# Protopanda_EasyEda_project.net
KiCad netlist of a schematic drawn in EasyEDA
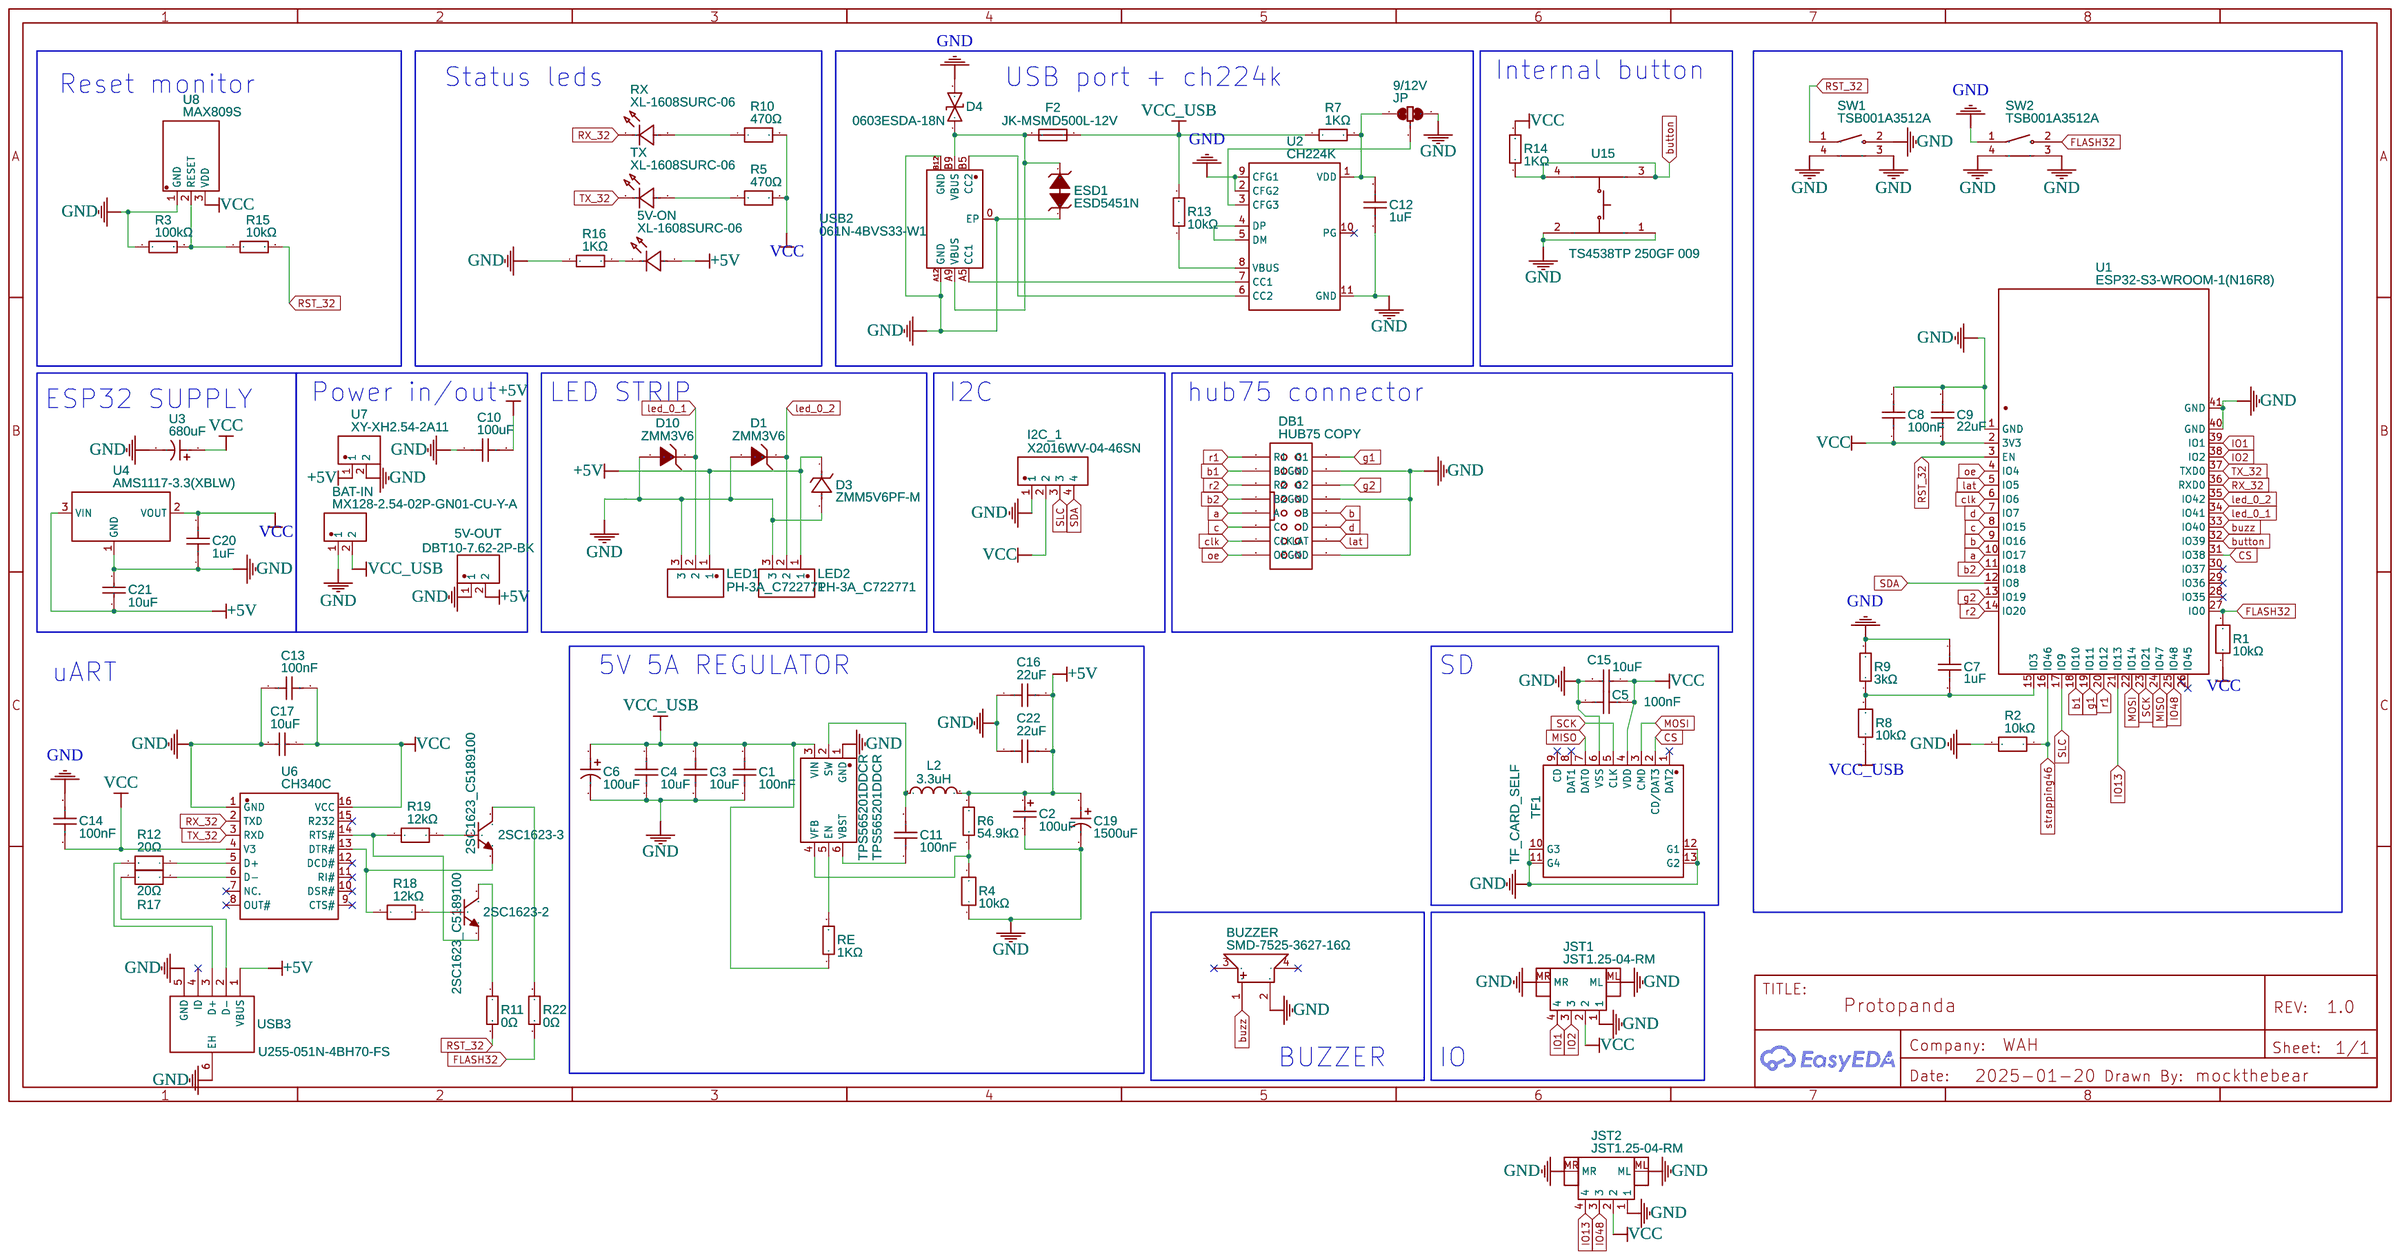
[diagram p0: schematic sheet]

(export (version "E")
  (design (tool "Eeschema 10.0.6"))
  (components
    (comp (ref "2SC1623-2")
      (value "2SC1623_C5189100")
      (fields (field (name "Manufacturer Part") "2SC1623") (field (name "Manufacturer") "HXY MOSFET(华轩阳电子)"))
      (libsource (lib "") (part "2SC1623_C5189100"))
    )
    (comp (ref "2SC1623-3")
      (value "2SC1623_C5189100")
      (fields (field (name "Manufacturer Part") "2SC1623") (field (name "Manufacturer") "HXY MOSFET(华轩阳电子)"))
      (libsource (lib "") (part "2SC1623_C5189100"))
    )
    (comp (ref "5V-ON")
      (value "XL-1608SURC-06")
      (fields (field (name "Manufacturer") "XINGLIGHT(成兴光)"))
      (libsource (lib "") (part "XL-1608SURC-06_2"))
    )
    (comp (ref "5V-OUT")
      (value "DBT10-7.62-2P-BK")
      (fields
        (field (name "Manufacturer Part") "DBT10-7.62-2P-BK-P")
        (field (name "Manufacturer") "DORABO(地博电气)")
      )
      (libsource (lib "") (part "DBT10-7.62-2P-BK"))
    )
    (comp (ref "9/12V") (value "JP") (libsource (lib "") (part "JUMPER-PAD-3-NOFULL_BOX_SILK")))
    (comp (ref "BAT-IN")
      (value "MX128-2.54-02P-GN01-CU-Y-A")
      (fields
        (field (name "Manufacturer Part") "MX128-2.54-02P-GN01-Cu-Y-A")
        (field (name "Manufacturer") "MAX(迈旭)")
      )
      (libsource (lib "") (part "MX128-2.54-02P-GN01-CU-Y-A"))
    )
    (comp (ref "BUZZER")
      (value "SMD-7525-3627-16Ω")
      (fields (field (name "Manufacturer") "S&S(海旭)"))
      (libsource (lib "") (part "SMD-7525-3627-16Ω"))
    )
    (comp (ref "C1")
      (value "100nF")
      (fields
        (field (name "Manufacturer Part") "CC0603KRX7R6BB104")
        (field (name "Manufacturer") "YAGEO(国巨)")
      )
      (libsource (lib "") (part "CC0603KRX7R6BB104_1"))
    )
    (comp (ref "C2")
      (value "100uF")
      (fields
        (field (name "Manufacturer Part") "T490A107M006ATE800")
        (field (name "Manufacturer") "KEMET(基美)")
      )
      (libsource (lib "") (part "T490A107M006ATE800"))
    )
    (comp (ref "C3")
      (value "10uF")
      (fields (field (name "Manufacturer Part") "CC0603CRNPO9BN5R1") (field (name "Manufacturer") "YAGEO"))
      (libsource (lib "") (part "CC0603CRNPO9BN5R1"))
    )
    (comp (ref "C4")
      (value "10uF")
      (fields (field (name "Manufacturer Part") "CC0603CRNPO9BN5R1") (field (name "Manufacturer") "YAGEO"))
      (libsource (lib "") (part "CC0603CRNPO9BN5R1"))
    )
    (comp (ref "C5")
      (value "100nF")
      (fields
        (field (name "Manufacturer Part") "CC0603KRX7R6BB104")
        (field (name "Manufacturer") "YAGEO(国巨)")
      )
      (libsource (lib "") (part "CC0603KRX7R6BB104"))
    )
    (comp (ref "C6")
      (value "100uF")
      (fields
        (field (name "Manufacturer Part") "RVT100UF25V67RV0011")
        (field (name "Manufacturer") "KNSCHA(科尼盛)")
      )
      (libsource (lib "") (part "RVT100UF25V67RV0011"))
    )
    (comp (ref "C7")
      (value "1uF")
      (fields
        (field (name "Manufacturer Part") "CS1608X7R105K250NRB")
        (field (name "Manufacturer") "Samwha Capacitor")
      )
      (libsource (lib "") (part "CS1608X7R105K250NRB"))
    )
    (comp (ref "C8")
      (value "100nF")
      (fields
        (field (name "Manufacturer Part") "CC0603KRX7R6BB104")
        (field (name "Manufacturer") "YAGEO(国巨)")
      )
      (libsource (lib "") (part "CC0603KRX7R6BB104_1"))
    )
    (comp (ref "C9")
      (value "22uF")
      (fields
        (field (name "Manufacturer Part") "GRM188R61A226ME15D")
        (field (name "Manufacturer") "muRata(村田)")
      )
      (libsource (lib "") (part "GRM188R61A226ME15D"))
    )
    (comp (ref "C10")
      (value "100uF")
      (fields
        (field (name "Manufacturer Part") "TCC1206X5R107M6R3HT")
        (field (name "Manufacturer") "CCTC(三环)")
      )
      (libsource (lib "") (part "TCC1206X5R107M6R3HT"))
    )
    (comp (ref "C11")
      (value "100nF")
      (fields
        (field (name "Manufacturer Part") "CC0603KRX7R6BB104")
        (field (name "Manufacturer") "YAGEO(国巨)")
      )
      (libsource (lib "") (part "CC0603KRX7R6BB104_1"))
    )
    (comp (ref "C12")
      (value "1uF")
      (fields (field (name "Manufacturer Part") "CC0603CRNPO9BN5R1") (field (name "Manufacturer") "YAGEO"))
      (libsource (lib "") (part "CC0603CRNPO9BN5R1"))
    )
    (comp (ref "C13")
      (value "100nF")
      (fields
        (field (name "Manufacturer Part") "CC0603KRX7R6BB104")
        (field (name "Manufacturer") "YAGEO(国巨)")
      )
      (libsource (lib "") (part "CC0603KRX7R6BB104"))
    )
    (comp (ref "C14")
      (value "100nF")
      (fields
        (field (name "Manufacturer Part") "CC0603KRX7R6BB104")
        (field (name "Manufacturer") "YAGEO(国巨)")
      )
      (libsource (lib "") (part "CC0603KRX7R6BB104_1"))
    )
    (comp (ref "C15")
      (value "10uF")
      (fields (field (name "Manufacturer Part") "CC0603MRX5R6BB106") (field (name "Manufacturer") "YAGEO"))
      (libsource (lib "") (part "CC0603MRX5R6BB106"))
    )
    (comp (ref "C16") (value "22uF") (libsource (lib "") (part "C_0805_US")))
    (comp (ref "C17")
      (value "10uF")
      (fields (field (name "Manufacturer Part") "CC0603KRX5R5BB106") (field (name "Manufacturer") "YAGEO"))
      (libsource (lib "") (part "CC0603KRX5R5BB106"))
    )
    (comp (ref "C19")
      (value "1500uF")
      (fields (field (name "Manufacturer Part") "189RV0022") (field (name "Manufacturer") "KNSCHA(科尼盛)"))
      (libsource (lib "") (part "189RV0022"))
    )
    (comp (ref "C20")
      (value "1uF")
      (fields
        (field (name "Manufacturer Part") "CS1608X7R105K250NRB")
        (field (name "Manufacturer") "Samwha Capacitor")
      )
      (libsource (lib "") (part "CS1608X7R105K250NRB_1"))
    )
    (comp (ref "C21")
      (value "10uF")
      (fields (field (name "Manufacturer Part") "CC0603MRX5R6BB106") (field (name "Manufacturer") "YAGEO"))
      (libsource (lib "") (part "CC0603MRX5R6BB106_1"))
    )
    (comp (ref "C22") (value "22uF") (libsource (lib "") (part "C_0805_US")))
    (comp (ref "D1")
      (value "ZMM3V6")
      (fields (field (name "Manufacturer Part") "ZMM3V6-M") (field (name "Manufacturer") "ST(先科)"))
      (libsource (lib "") (part "ZMM3V6"))
    )
    (comp (ref "D3")
      (value "ZMM5V6PF-M")
      (fields (field (name "Manufacturer") "ST(先科)"))
      (libsource (lib "") (part "ZMM5V6PF-M"))
    )
    (comp (ref "D4")
      (value "0603ESDA-18N")
      (fields (field (name "Manufacturer") "BORN(伯恩半导体)"))
      (libsource (lib "") (part "0603ESDA-18N"))
    )
    (comp (ref "D10")
      (value "ZMM3V6")
      (fields (field (name "Manufacturer Part") "ZMM3V6-M") (field (name "Manufacturer") "ST(先科)"))
      (libsource (lib "") (part "ZMM3V6"))
    )
    (comp (ref "DB1") (value "HUB75 COPY") (libsource (lib "") (part "HUB75 COPY")))
    (comp (ref "ESD1")
      (value "ESD5451N")
      (fields (field (name "Manufacturer") "UMW(广东友台半导体)"))
      (libsource (lib "") (part "ESD5451N"))
    )
    (comp (ref "F2")
      (value "JK-MSMD500L-12V")
      (fields (field (name "Manufacturer") "JK(金科)"))
      (libsource (lib "") (part "JK-MSMD500L-12V"))
    )
    (comp (ref "I2C_1")
      (value "X2016WV-04-46SN")
      (fields (field (name "Manufacturer") "XKB Connectivity(中国星坤)"))
      (libsource (lib "") (part "X2016WV-04-46SN"))
    )
    (comp (ref "JST1") (value "JST1.25-04-RM") (libsource (lib "") (part "JST1.25-04-RM")))
    (comp (ref "JST2") (value "JST1.25-04-RM") (libsource (lib "") (part "JST1.25-04-RM")))
    (comp (ref "L2")
      (value "3.3uH")
      (fields
        (field (name "Manufacturer Part") "PSPMAA1040H-3R3M-ANP")
        (field (name "Manufacturer") "PROD(谱罗德)")
      )
      (libsource (lib "") (part "PSPMAA1040H-3R3M-ANP"))
    )
    (comp (ref "LED1")
      (value "PH-3A_C722771")
      (fields (field (name "Manufacturer Part") "PH-3A") (field (name "Manufacturer") "CAX(创都)"))
      (libsource (lib "") (part "PH-3A_C722771"))
    )
    (comp (ref "LED2")
      (value "PH-3A_C722771")
      (fields (field (name "Manufacturer Part") "PH-3A") (field (name "Manufacturer") "CAX(创都)"))
      (libsource (lib "") (part "PH-3A_C722771"))
    )
    (comp (ref "R1")
      (value "10kΩ")
      (fields (field (name "Manufacturer Part") "FRC0603F4992TS") (field (name "Manufacturer") "FOJAN(富捷)"))
      (libsource (lib "") (part "FRC0603F4992TS"))
    )
    (comp (ref "R2")
      (value "10kΩ")
      (fields (field (name "Manufacturer Part") "FRC0603F4992TS") (field (name "Manufacturer") "FOJAN(富捷)"))
      (libsource (lib "") (part "FRC0603F4992TS_1"))
    )
    (comp (ref "R3")
      (value "100kΩ")
      (fields
        (field (name "Manufacturer Part") "CL0603JN100KP")
        (field (name "Manufacturer") "ResistorToday")
      )
      (libsource (lib "") (part "PTFR0603B10K0P9_1"))
    )
    (comp (ref "R4")
      (value "10kΩ")
      (fields (field (name "Manufacturer Part") "FRC0603F4992TS") (field (name "Manufacturer") "FOJAN(富捷)"))
      (libsource (lib "") (part "FRC0603F4992TS"))
    )
    (comp (ref "R5")
      (value "470Ω")
      (fields (field (name "Manufacturer Part") "CL0603JN470RP") (field (name "Manufacturer") "昶龙科技"))
      (libsource (lib "") (part "CL0603JN470RP"))
    )
    (comp (ref "R6")
      (value "54.9kΩ")
      (fields
        (field (name "Manufacturer Part") "RCT03365KFLF")
        (field (name "Manufacturer") "Hong Kong Resistors")
      )
      (libsource (lib "") (part "RCT03365KFLF"))
    )
    (comp (ref "R7")
      (value "1KΩ")
      (fields (field (name "Manufacturer Part") "HRC0603J102 ENTN") (field (name "Manufacturer") "HWA CHN"))
      (libsource (lib "") (part "CR0603FA56R0G"))
    )
    (comp (ref "R8")
      (value "10kΩ")
      (fields (field (name "Manufacturer Part") "FRC0603F4992TS") (field (name "Manufacturer") "FOJAN(富捷)"))
      (libsource (lib "") (part "FRC0603F4992TS"))
    )
    (comp (ref "R9")
      (value "3kΩ")
      (fields (field (name "Manufacturer Part") "RTT03302JTP") (field (name "Manufacturer") "RALEC(旺诠)"))
      (libsource (lib "") (part "RTT03302JTP"))
    )
    (comp (ref "R10")
      (value "470Ω")
      (fields (field (name "Manufacturer Part") "CL0603JN470RP") (field (name "Manufacturer") "昶龙科技"))
      (libsource (lib "") (part "CL0603JN470RP"))
    )
    (comp (ref "R11")
      (value "0Ω")
      (fields
        (field (name "Manufacturer Part") "AECR0603F100RK9")
        (field (name "Manufacturer") "ResistorToday")
      )
      (libsource (lib "") (part "AECR0603F100RK9"))
    )
    (comp (ref "R12")
      (value "20Ω")
      (fields (field (name "Manufacturer Part") "SCR0603F20R") (field (name "Manufacturer") "VO(翔胜)"))
      (libsource (lib "") (part "SCR0603F20R_1"))
    )
    (comp (ref "R13")
      (value "10kΩ")
      (fields
        (field (name "Manufacturer Part") "PTFR0603B10K0P9")
        (field (name "Manufacturer") "ResistorToday")
      )
      (libsource (lib "") (part "PTFR0603B10K0P9"))
    )
    (comp (ref "R14")
      (value "1KΩ")
      (fields (field (name "Manufacturer Part") "HRC0603J102 ENTN") (field (name "Manufacturer") "HWA CHN"))
      (libsource (lib "") (part "CR0603FA56R0G_1"))
    )
    (comp (ref "R15")
      (value "10kΩ")
      (fields
        (field (name "Manufacturer Part") "PTFR0603B10K0P9")
        (field (name "Manufacturer") "ResistorToday")
      )
      (libsource (lib "") (part "PTFR0603B10K0P9_1"))
    )
    (comp (ref "R16")
      (value "1KΩ")
      (fields (field (name "Manufacturer Part") "HRC0603J102 ENTN") (field (name "Manufacturer") "HWA CHN"))
      (libsource (lib "") (part "CR0603FA56R0G"))
    )
    (comp (ref "R17")
      (value "20Ω")
      (fields (field (name "Manufacturer Part") "SCR0603F20R") (field (name "Manufacturer") "VO(翔胜)"))
      (libsource (lib "") (part "SCR0603F20R"))
    )
    (comp (ref "R18")
      (value "12kΩ")
      (fields (field (name "Manufacturer Part") "FRC0603J123 TS") (field (name "Manufacturer") "FOJAN(富捷)"))
      (libsource (lib "") (part "FRC0603J123 TS"))
    )
    (comp (ref "R19")
      (value "12kΩ")
      (fields (field (name "Manufacturer Part") "FRC0603J123 TS") (field (name "Manufacturer") "FOJAN(富捷)"))
      (libsource (lib "") (part "FRC0603J123 TS"))
    )
    (comp (ref "R22")
      (value "0Ω")
      (fields
        (field (name "Manufacturer Part") "AECR0603F100RK9")
        (field (name "Manufacturer") "ResistorToday")
      )
      (libsource (lib "") (part "AECR0603F100RK9_1"))
    )
    (comp (ref "RE")
      (value "1KΩ")
      (fields (field (name "Manufacturer Part") "HRC0603J102 ENTN") (field (name "Manufacturer") "HWA CHN"))
      (libsource (lib "") (part "CR0603FA56R0G_2"))
    )
    (comp (ref "RX")
      (value "XL-1608SURC-06")
      (fields (field (name "Manufacturer") "XINGLIGHT(成兴光)"))
      (libsource (lib "") (part "XL-1608SURC-06_1"))
    )
    (comp (ref "SW1")
      (value "TSB001A3512A")
      (fields (field (name "Manufacturer") "BZCN(博众电气)"))
      (libsource (lib "") (part "TSB001A3512A"))
    )
    (comp (ref "SW2")
      (value "TSB001A3512A")
      (fields (field (name "Manufacturer") "BZCN(博众电气)"))
      (libsource (lib "") (part "TSB001A3512A"))
    )
    (comp (ref "TF1") (value "TF_CARD_SELF") (libsource (lib "") (part "TF_CARD_SELF")))
    (comp (ref "TPS565201DDCR")
      (value "TPS565201DDCR")
      (fields (field (name "Manufacturer") "TI(德州仪器)"))
      (libsource (lib "") (part "TPS565201DDCR"))
    )
    (comp (ref "TX")
      (value "XL-1608SURC-06")
      (fields (field (name "Manufacturer") "XINGLIGHT(成兴光)"))
      (libsource (lib "") (part "XL-1608SURC-06"))
    )
    (comp (ref "U1")
      (value "ESP32-S3-WROOM-1(N16R8)")
      (fields
        (field (name "Manufacturer Part") "ESP32-S3-WROOM-1-N16R8")
        (field (name "Manufacturer") "ESPRESSIF(乐鑫)")
      )
      (libsource (lib "") (part "ESP32-S3-WROOM-1(N16R8)"))
    )
    (comp (ref "U2")
      (value "CH224K")
      (fields (field (name "Manufacturer") "WCH(南京沁恒)"))
      (libsource (lib "") (part "CH224K"))
    )
    (comp (ref "U3")
      (value "680uF")
      (fields (field (name "Manufacturer Part") "189RV0015") (field (name "Manufacturer") "KNSCHA(科尼盛)"))
      (libsource (lib "") (part "189RV0015"))
    )
    (comp (ref "U4")
      (value "AMS1117-3.3(XBLW)")
      (fields (field (name "Manufacturer") "XBLW(芯伯乐)"))
      (libsource (lib "") (part "AMS1117-3.3(XBLW)"))
    )
    (comp (ref "U6")
      (value "CH340C")
      (fields (field (name "Manufacturer") "WCH(南京沁恒)"))
      (libsource (lib "") (part "CH340C"))
    )
    (comp (ref "U7")
      (value "XY-XH2.54-2A11")
      (fields (field (name "Manufacturer") "XYECONN(辛译)"))
      (libsource (lib "") (part "XY-XH2.54-2A11"))
    )
    (comp (ref "U8")
      (value "MAX809S")
      (fields (field (name "Manufacturer") "UMW(广东友台半导体)"))
      (libsource (lib "") (part "MAX809S"))
    )
    (comp (ref "U15")
      (value "TS4538TP 250GF 009")
      (fields
        (field (name "Manufacturer Part") "TS4538TP 250gf 009")
        (field (name "Manufacturer") "SHOU HAN(首韩)")
      )
      (libsource (lib "") (part "TS4538TP 250GF 009"))
    )
    (comp (ref "USB2")
      (value "061N-4BVS33-W1")
      (fields (field (name "Manufacturer") "HanElectricity(瀚源)"))
      (libsource (lib "") (part "061N-4BVS33-W1"))
    )
    (comp (ref "USB3")
      (value "U255-051N-4BH70-FS")
      (fields (field (name "Manufacturer") "XKB Connection(中国星坤)"))
      (libsource (lib "") (part "U255-051N-4BH70-FS"))
    )
  )
  (nets
    (net (code "1") (name "+5V") (class "Default")
      (node (ref "5V-ON") (pin "2") (pinfunction "A_2") (pintype "unspecified"))
      (node (ref "5V-OUT") (pin "2") (pinfunction "2_2") (pintype "unspecified"))
      (node (ref "C10") (pin "2") (pinfunction "2_2") (pintype "unspecified"))
      (node (ref "C16") (pin "2") (pinfunction "2_2") (pintype "unspecified"))
      (node (ref "C19") (pin "1") (pinfunction "1_1") (pintype "input"))
      (node (ref "C2") (pin "1") (pinfunction "1_1") (pintype "input"))
      (node (ref "C21") (pin "2") (pinfunction "2_2") (pintype "input"))
      (node (ref "C22") (pin "2") (pinfunction "2_2") (pintype "unspecified"))
      (node (ref "D3") (pin "1") (pinfunction "C_1") (pintype "unspecified"))
      (node (ref "L2") (pin "2") (pinfunction "2_2") (pintype "unspecified"))
      (node (ref "LED1") (pin "1") (pinfunction "1_1") (pintype "unspecified"))
      (node (ref "LED2") (pin "1") (pinfunction "1_1") (pintype "unspecified"))
      (node (ref "R6") (pin "2") (pinfunction "2_2") (pintype "unspecified"))
      (node (ref "U4") (pin "3") (pinfunction "VIN_3") (pintype "unspecified"))
      (node (ref "U7") (pin "1") (pinfunction "1_1") (pintype "unspecified"))
      (node (ref "USB3") (pin "1") (pinfunction "VBUS_1") (pintype "unspecified"))
    )
    (net (code "2") (name "CS") (class "Default")
      (node (ref "TF1") (pin "2") (pinfunction "CD/DAT3_2") (pintype "unspecified"))
      (node (ref "U1") (pin "31") (pinfunction "IO38_31") (pintype "unspecified"))
    )
    (net (code "3") (name "FLASH32") (class "Default")
      (node (ref "R1") (pin "2") (pinfunction "2_2") (pintype "unspecified"))
      (node (ref "R22") (pin "1") (pinfunction "1_1") (pintype "unspecified"))
      (node (ref "SW2") (pin "2") (pinfunction "2_2") (pintype "unspecified"))
      (node (ref "U1") (pin "27") (pinfunction "IO0_27") (pintype "unspecified"))
    )
    (net (code "4") (name "GND") (class "Default")
      (node (ref "5V-OUT") (pin "1") (pinfunction "1_1") (pintype "unspecified"))
      (node (ref "9/12V") (pin "3") (pinfunction "3_3") (pintype "unspecified"))
      (node (ref "BAT-IN") (pin "1") (pinfunction "1_1") (pintype "unspecified"))
      (node (ref "BUZZER") (pin "2") (pinfunction "2_2") (pintype "unspecified"))
      (node (ref "C1") (pin "1") (pinfunction "1_1") (pintype "unspecified"))
      (node (ref "C10") (pin "1") (pinfunction "1_1") (pintype "unspecified"))
      (node (ref "C12") (pin "2") (pinfunction "2_2") (pintype "unspecified"))
      (node (ref "C13") (pin "1") (pinfunction "1_1") (pintype "unspecified"))
      (node (ref "C14") (pin "2") (pinfunction "2_2") (pintype "unspecified"))
      (node (ref "C15") (pin "2") (pinfunction "2_2") (pintype "input"))
      (node (ref "C16") (pin "1") (pinfunction "1_1") (pintype "unspecified"))
      (node (ref "C17") (pin "2") (pinfunction "2_2") (pintype "input"))
      (node (ref "C19") (pin "2") (pinfunction "2_2") (pintype "input"))
      (node (ref "C2") (pin "2") (pinfunction "2_2") (pintype "input"))
      (node (ref "C20") (pin "1") (pinfunction "1_1") (pintype "unspecified"))
      (node (ref "C21") (pin "1") (pinfunction "1_1") (pintype "input"))
      (node (ref "C22") (pin "1") (pinfunction "1_1") (pintype "unspecified"))
      (node (ref "C3") (pin "2") (pinfunction "2_2") (pintype "unspecified"))
      (node (ref "C4") (pin "2") (pinfunction "2_2") (pintype "unspecified"))
      (node (ref "C5") (pin "1") (pinfunction "1_1") (pintype "unspecified"))
      (node (ref "C6") (pin "2") (pinfunction "2_2") (pintype "input"))
      (node (ref "C7") (pin "1") (pinfunction "1_1") (pintype "unspecified"))
      (node (ref "C8") (pin "2") (pinfunction "2_2") (pintype "unspecified"))
      (node (ref "C9") (pin "1") (pinfunction "1_1") (pintype "unspecified"))
      (node (ref "D1") (pin "2") (pinfunction "A_2") (pintype "unspecified"))
      (node (ref "D10") (pin "2") (pinfunction "A_2") (pintype "unspecified"))
      (node (ref "D3") (pin "2") (pinfunction "A_2") (pintype "unspecified"))
      (node (ref "D4") (pin "2") (pinfunction "2_2") (pintype "unspecified"))
      (node (ref "DB1") (pin "13") (pinfunction "GND_13") (pintype "unspecified"))
      (node (ref "DB1") (pin "15") (pinfunction "GND_15") (pintype "unspecified"))
      (node (ref "DB1") (pin "9") (pinfunction "GND_9") (pintype "unspecified"))
      (node (ref "ESD1") (pin "1") (pinfunction "1_1") (pintype "unspecified"))
      (node (ref "I2C_1") (pin "1") (pinfunction "1_1") (pintype "unspecified"))
      (node (ref "JST1") (pin "1") (pinfunction "1_1") (pintype "unspecified"))
      (node (ref "JST1") (pin "ML") (pinfunction "ML_ML") (pintype "unspecified"))
      (node (ref "JST1") (pin "MR") (pinfunction "MR_MR") (pintype "unspecified"))
      (node (ref "JST2") (pin "1") (pinfunction "1_1") (pintype "unspecified"))
      (node (ref "JST2") (pin "ML") (pinfunction "ML_ML") (pintype "unspecified"))
      (node (ref "JST2") (pin "MR") (pinfunction "MR_MR") (pintype "unspecified"))
      (node (ref "LED1") (pin "3") (pinfunction "3_3") (pintype "unspecified"))
      (node (ref "LED2") (pin "3") (pinfunction "3_3") (pintype "unspecified"))
      (node (ref "R16") (pin "1") (pinfunction "1_1") (pintype "input"))
      (node (ref "R2") (pin "2") (pinfunction "2_2") (pintype "unspecified"))
      (node (ref "R3") (pin "1") (pinfunction "1_1") (pintype "unspecified"))
      (node (ref "R4") (pin "1") (pinfunction "1_1") (pintype "unspecified"))
      (node (ref "R9") (pin "2") (pinfunction "2_2") (pintype "input"))
      (node (ref "SW1") (pin "2") (pinfunction "2_2") (pintype "unspecified"))
      (node (ref "SW1") (pin "3") (pinfunction "3_3") (pintype "unspecified"))
      (node (ref "SW1") (pin "4") (pinfunction "4_4") (pintype "unspecified"))
      (node (ref "SW2") (pin "1") (pinfunction "1_1") (pintype "unspecified"))
      (node (ref "SW2") (pin "3") (pinfunction "3_3") (pintype "unspecified"))
      (node (ref "SW2") (pin "4") (pinfunction "4_4") (pintype "unspecified"))
      (node (ref "TF1") (pin "10") (pinfunction "G3_10") (pintype "unspecified"))
      (node (ref "TF1") (pin "11") (pinfunction "G4_11") (pintype "unspecified"))
      (node (ref "TF1") (pin "12") (pinfunction "G1_12") (pintype "unspecified"))
      (node (ref "TF1") (pin "13") (pinfunction "G2_13") (pintype "unspecified"))
      (node (ref "TF1") (pin "6") (pinfunction "VSS_6") (pintype "unspecified"))
      (node (ref "TPS565201DDCR") (pin "1") (pinfunction "GND_1") (pintype "unspecified"))
      (node (ref "U1") (pin "1") (pinfunction "GND_1") (pintype "unspecified"))
      (node (ref "U1") (pin "40") (pinfunction "GND_40") (pintype "unspecified"))
      (node (ref "U1") (pin "41") (pinfunction "GND_41") (pintype "unspecified"))
      (node (ref "U15") (pin "1") (pinfunction "1_1") (pintype "unspecified"))
      (node (ref "U15") (pin "2") (pinfunction "2_2") (pintype "unspecified"))
      (node (ref "U2") (pin "11") (pinfunction "GND_11") (pintype "unspecified"))
      (node (ref "U2") (pin "2") (pinfunction "CFG2_2") (pintype "unspecified"))
      (node (ref "U2") (pin "9") (pinfunction "CFG1_9") (pintype "unspecified"))
      (node (ref "U3") (pin "2") (pinfunction "2_2") (pintype "input"))
      (node (ref "U4") (pin "1") (pinfunction "GND_1") (pintype "unspecified"))
      (node (ref "U6") (pin "1") (pinfunction "GND_1") (pintype "unspecified"))
      (node (ref "U7") (pin "2") (pinfunction "2_2") (pintype "unspecified"))
      (node (ref "U8") (pin "1") (pinfunction "GND_1") (pintype "unspecified"))
      (node (ref "USB2") (pin "0") (pinfunction "EP_0") (pintype "unspecified"))
      (node (ref "USB2") (pin "A12") (pinfunction "GND_A12") (pintype "unspecified"))
      (node (ref "USB2") (pin "B12") (pinfunction "GND_B12") (pintype "unspecified"))
      (node (ref "USB3") (pin "5") (pinfunction "GND_5") (pintype "unspecified"))
      (node (ref "USB3") (pin "6") (pinfunction "EH_6") (pintype "unspecified"))
    )
    (net (code "5") (name "IO1") (class "Default")
      (node (ref "JST1") (pin "4") (pinfunction "4_4") (pintype "unspecified"))
      (node (ref "U1") (pin "39") (pinfunction "IO1_39") (pintype "unspecified"))
    )
    (net (code "6") (name "IO2") (class "Default")
      (node (ref "JST1") (pin "3") (pinfunction "3_3") (pintype "unspecified"))
      (node (ref "U1") (pin "38") (pinfunction "IO2_38") (pintype "unspecified"))
    )
    (net (code "7") (name "IO13") (class "Default")
      (node (ref "JST2") (pin "4") (pinfunction "4_4") (pintype "unspecified"))
      (node (ref "U1") (pin "21") (pinfunction "IO13_21") (pintype "unspecified"))
    )
    (net (code "8") (name "IO48") (class "Default")
      (node (ref "JST2") (pin "3") (pinfunction "3_3") (pintype "unspecified"))
      (node (ref "U1") (pin "25") (pinfunction "IO48_25") (pintype "unspecified"))
    )
    (net (code "9") (name "MISO") (class "Default")
      (node (ref "TF1") (pin "7") (pinfunction "DAT0_7") (pintype "unspecified"))
      (node (ref "U1") (pin "24") (pinfunction "IO47_24") (pintype "unspecified"))
    )
    (net (code "10") (name "MOSI") (class "Default")
      (node (ref "TF1") (pin "3") (pinfunction "CMD_3") (pintype "unspecified"))
      (node (ref "U1") (pin "22") (pinfunction "IO14_22") (pintype "unspecified"))
    )
    (net (code "11") (name "Net-(2SC1623-2-B)") (class "Default")
      (node (ref "2SC1623-2") (pin "1") (pinfunction "B_1") (pintype "input"))
      (node (ref "R18") (pin "2") (pinfunction "2_2") (pintype "unspecified"))
    )
    (net (code "12") (name "Net-(2SC1623-2-C)") (class "Default")
      (node (ref "2SC1623-2") (pin "3") (pinfunction "C_3") (pintype "input"))
      (node (ref "R11") (pin "1") (pinfunction "1_1") (pintype "unspecified"))
    )
    (net (code "13") (name "Net-(2SC1623-2-E)") (class "Default")
      (node (ref "2SC1623-2") (pin "2") (pinfunction "E_2") (pintype "input"))
      (node (ref "R19") (pin "1") (pinfunction "1_1") (pintype "unspecified"))
      (node (ref "U6") (pin "14") (pinfunction "RTS#_14") (pintype "unspecified"))
    )
    (net (code "14") (name "Net-(2SC1623-3-B)") (class "Default")
      (node (ref "2SC1623-3") (pin "1") (pinfunction "B_1") (pintype "input"))
      (node (ref "R19") (pin "2") (pinfunction "2_2") (pintype "unspecified"))
    )
    (net (code "15") (name "Net-(2SC1623-3-C)") (class "Default")
      (node (ref "2SC1623-3") (pin "3") (pinfunction "C_3") (pintype "input"))
      (node (ref "R22") (pin "2") (pinfunction "2_2") (pintype "unspecified"))
    )
    (net (code "16") (name "Net-(2SC1623-3-E)") (class "Default")
      (node (ref "2SC1623-3") (pin "2") (pinfunction "E_2") (pintype "input"))
      (node (ref "R18") (pin "1") (pinfunction "1_1") (pintype "unspecified"))
      (node (ref "U6") (pin "13") (pinfunction "DTR#_13") (pintype "unspecified"))
    )
    (net (code "17") (name "Net-(5V-ON-K)") (class "Default")
      (node (ref "5V-ON") (pin "1") (pinfunction "K_1") (pintype "unspecified"))
      (node (ref "R16") (pin "2") (pinfunction "2_2") (pintype "input"))
    )
    (net (code "18") (name "Net-(D4-Pad1)") (class "Default")
      (node (ref "D4") (pin "1") (pinfunction "1_1") (pintype "unspecified"))
      (node (ref "ESD1") (pin "2") (pinfunction "2_2") (pintype "unspecified"))
      (node (ref "F2") (pin "2") (pinfunction "2_2") (pintype "unspecified"))
      (node (ref "USB2") (pin "A9") (pinfunction "VBUS_A9") (pintype "unspecified"))
      (node (ref "USB2") (pin "B9") (pinfunction "VBUS_B9") (pintype "unspecified"))
    )
    (net (code "19") (name "Net-(RX-A)") (class "Default")
      (node (ref "R10") (pin "1") (pinfunction "1_1") (pintype "unspecified"))
      (node (ref "RX") (pin "2") (pinfunction "A_2") (pintype "unspecified"))
    )
    (net (code "20") (name "Net-(TPS565201DDCR-EN)") (class "Default")
      (node (ref "RE") (pin "2") (pinfunction "2_2") (pintype "input"))
      (node (ref "TPS565201DDCR") (pin "5") (pinfunction "EN_5") (pintype "unspecified"))
    )
    (net (code "21") (name "Net-(TPS565201DDCR-SW)") (class "Default")
      (node (ref "C11") (pin "2") (pinfunction "2_2") (pintype "unspecified"))
      (node (ref "L2") (pin "1") (pinfunction "1_1") (pintype "unspecified"))
      (node (ref "TPS565201DDCR") (pin "2") (pinfunction "SW_2") (pintype "unspecified"))
    )
    (net (code "22") (name "Net-(TPS565201DDCR-VBST)") (class "Default")
      (node (ref "C11") (pin "1") (pinfunction "1_1") (pintype "unspecified"))
      (node (ref "TPS565201DDCR") (pin "6") (pinfunction "VBST_6") (pintype "unspecified"))
    )
    (net (code "23") (name "Net-(TPS565201DDCR-VFB)") (class "Default")
      (node (ref "R4") (pin "2") (pinfunction "2_2") (pintype "unspecified"))
      (node (ref "R6") (pin "1") (pinfunction "1_1") (pintype "unspecified"))
      (node (ref "TPS565201DDCR") (pin "4") (pinfunction "VFB_4") (pintype "unspecified"))
    )
    (net (code "24") (name "Net-(TX-A)") (class "Default")
      (node (ref "R5") (pin "1") (pinfunction "1_1") (pintype "unspecified"))
      (node (ref "TX") (pin "2") (pinfunction "A_2") (pintype "unspecified"))
    )
    (net (code "25") (name "Net-(U1-IO3)") (class "Default")
      (node (ref "C7") (pin "2") (pinfunction "2_2") (pintype "unspecified"))
      (node (ref "R8") (pin "2") (pinfunction "2_2") (pintype "unspecified"))
      (node (ref "R9") (pin "1") (pinfunction "1_1") (pintype "input"))
      (node (ref "U1") (pin "15") (pinfunction "IO3_15") (pintype "unspecified"))
    )
    (net (code "26") (name "Net-(U2-CC1)") (class "Default")
      (node (ref "U2") (pin "7") (pinfunction "CC1_7") (pintype "unspecified"))
      (node (ref "USB2") (pin "A5") (pinfunction "CC1_A5") (pintype "unspecified"))
    )
    (net (code "27") (name "Net-(U2-CC2)") (class "Default")
      (node (ref "U2") (pin "6") (pinfunction "CC2_6") (pintype "unspecified"))
      (node (ref "USB2") (pin "B5") (pinfunction "CC2_B5") (pintype "unspecified"))
    )
    (net (code "28") (name "Net-(U2-CFG3)") (class "Default")
      (node (ref "9/12V") (pin "2") (pinfunction "2_2") (pintype "unspecified"))
      (node (ref "U2") (pin "3") (pinfunction "CFG3_3") (pintype "unspecified"))
    )
    (net (code "29") (name "Net-(U2-DM)") (class "Default")
      (node (ref "U2") (pin "4") (pinfunction "DP_4") (pintype "unspecified"))
      (node (ref "U2") (pin "5") (pinfunction "DM_5") (pintype "unspecified"))
    )
    (net (code "30") (name "Net-(U2-VBUS)") (class "Default")
      (node (ref "R13") (pin "1") (pinfunction "1_1") (pintype "unspecified"))
      (node (ref "U2") (pin "8") (pinfunction "VBUS_8") (pintype "unspecified"))
    )
    (net (code "31") (name "Net-(U2-VDD)") (class "Default")
      (node (ref "9/12V") (pin "1") (pinfunction "1_1") (pintype "unspecified"))
      (node (ref "C12") (pin "1") (pinfunction "1_1") (pintype "unspecified"))
      (node (ref "R7") (pin "2") (pinfunction "2_2") (pintype "input"))
      (node (ref "U2") (pin "1") (pinfunction "VDD_1") (pintype "unspecified"))
    )
    (net (code "32") (name "Net-(U6-D+)") (class "Default")
      (node (ref "R12") (pin "1") (pinfunction "1_1") (pintype "unspecified"))
      (node (ref "U6") (pin "5") (pinfunction "D+_5") (pintype "unspecified"))
    )
    (net (code "33") (name "Net-(U6-D-)") (class "Default")
      (node (ref "R17") (pin "2") (pinfunction "2_2") (pintype "unspecified"))
      (node (ref "U6") (pin "6") (pinfunction "D-_6") (pintype "unspecified"))
    )
    (net (code "34") (name "Net-(U8-RESET)") (class "Default")
      (node (ref "R15") (pin "1") (pinfunction "1_1") (pintype "unspecified"))
      (node (ref "R3") (pin "2") (pinfunction "2_2") (pintype "unspecified"))
      (node (ref "U8") (pin "2") (pinfunction "RESET_2") (pintype "unspecified"))
    )
    (net (code "35") (name "Net-(USB3-D+)") (class "Default")
      (node (ref "R12") (pin "2") (pinfunction "2_2") (pintype "unspecified"))
      (node (ref "USB3") (pin "3") (pinfunction "D+_3") (pintype "unspecified"))
    )
    (net (code "36") (name "Net-(USB3-D-)") (class "Default")
      (node (ref "R17") (pin "1") (pinfunction "1_1") (pintype "unspecified"))
      (node (ref "USB3") (pin "2") (pinfunction "D-_2") (pintype "unspecified"))
    )
    (net (code "37") (name "RST_32") (class "Default")
      (node (ref "R11") (pin "2") (pinfunction "2_2") (pintype "unspecified"))
      (node (ref "R15") (pin "2") (pinfunction "2_2") (pintype "unspecified"))
      (node (ref "SW1") (pin "1") (pinfunction "1_1") (pintype "unspecified"))
      (node (ref "U1") (pin "3") (pinfunction "EN_3") (pintype "unspecified"))
    )
    (net (code "38") (name "RX_32") (class "Default")
      (node (ref "RX") (pin "1") (pinfunction "K_1") (pintype "unspecified"))
      (node (ref "U1") (pin "36") (pinfunction "RXD0_36") (pintype "unspecified"))
      (node (ref "U6") (pin "2") (pinfunction "TXD_2") (pintype "unspecified"))
    )
    (net (code "39") (name "SCK") (class "Default")
      (node (ref "TF1") (pin "5") (pinfunction "CLK_5") (pintype "unspecified"))
      (node (ref "U1") (pin "23") (pinfunction "IO21_23") (pintype "unspecified"))
    )
    (net (code "40") (name "SDA") (class "Default")
      (node (ref "I2C_1") (pin "4") (pinfunction "4_4") (pintype "unspecified"))
      (node (ref "U1") (pin "12") (pinfunction "IO8_12") (pintype "unspecified"))
    )
    (net (code "41") (name "SLC") (class "Default")
      (node (ref "I2C_1") (pin "3") (pinfunction "3_3") (pintype "unspecified"))
      (node (ref "U1") (pin "17") (pinfunction "IO9_17") (pintype "unspecified"))
    )
    (net (code "42") (name "TX_32") (class "Default")
      (node (ref "TX") (pin "1") (pinfunction "K_1") (pintype "unspecified"))
      (node (ref "U1") (pin "37") (pinfunction "TXD0_37") (pintype "unspecified"))
      (node (ref "U6") (pin "3") (pinfunction "RXD_3") (pintype "unspecified"))
    )
    (net (code "43") (name "VCC") (class "Default")
      (node (ref "C13") (pin "2") (pinfunction "2_2") (pintype "unspecified"))
      (node (ref "C14") (pin "1") (pinfunction "1_1") (pintype "unspecified"))
      (node (ref "C15") (pin "1") (pinfunction "1_1") (pintype "input"))
      (node (ref "C17") (pin "1") (pinfunction "1_1") (pintype "input"))
      (node (ref "C20") (pin "2") (pinfunction "2_2") (pintype "unspecified"))
      (node (ref "C5") (pin "2") (pinfunction "2_2") (pintype "unspecified"))
      (node (ref "C8") (pin "1") (pinfunction "1_1") (pintype "unspecified"))
      (node (ref "C9") (pin "2") (pinfunction "2_2") (pintype "unspecified"))
      (node (ref "I2C_1") (pin "2") (pinfunction "2_2") (pintype "unspecified"))
      (node (ref "JST1") (pin "2") (pinfunction "2_2") (pintype "unspecified"))
      (node (ref "JST2") (pin "2") (pinfunction "2_2") (pintype "unspecified"))
      (node (ref "R1") (pin "1") (pinfunction "1_1") (pintype "unspecified"))
      (node (ref "R10") (pin "2") (pinfunction "2_2") (pintype "unspecified"))
      (node (ref "R14") (pin "2") (pinfunction "2_2") (pintype "input"))
      (node (ref "R5") (pin "2") (pinfunction "2_2") (pintype "unspecified"))
      (node (ref "TF1") (pin "4") (pinfunction "VDD_4") (pintype "unspecified"))
      (node (ref "U1") (pin "2") (pinfunction "3V3_2") (pintype "unspecified"))
      (node (ref "U3") (pin "1") (pinfunction "1_1") (pintype "input"))
      (node (ref "U4") (pin "2") (pinfunction "VOUT_2") (pintype "unspecified"))
      (node (ref "U6") (pin "16") (pinfunction "VCC_16") (pintype "unspecified"))
      (node (ref "U6") (pin "4") (pinfunction "V3_4") (pintype "unspecified"))
      (node (ref "U8") (pin "3") (pinfunction "VDD_3") (pintype "unspecified"))
    )
    (net (code "44") (name "VCC_USB") (class "Default")
      (node (ref "BAT-IN") (pin "2") (pinfunction "2_2") (pintype "unspecified"))
      (node (ref "C1") (pin "2") (pinfunction "2_2") (pintype "unspecified"))
      (node (ref "C3") (pin "1") (pinfunction "1_1") (pintype "unspecified"))
      (node (ref "C4") (pin "1") (pinfunction "1_1") (pintype "unspecified"))
      (node (ref "C6") (pin "1") (pinfunction "1_1") (pintype "input"))
      (node (ref "F2") (pin "1") (pinfunction "1_1") (pintype "unspecified"))
      (node (ref "R13") (pin "2") (pinfunction "2_2") (pintype "unspecified"))
      (node (ref "R7") (pin "1") (pinfunction "1_1") (pintype "input"))
      (node (ref "R8") (pin "1") (pinfunction "1_1") (pintype "unspecified"))
      (node (ref "RE") (pin "1") (pinfunction "1_1") (pintype "input"))
      (node (ref "TPS565201DDCR") (pin "3") (pinfunction "VIN_3") (pintype "unspecified"))
    )
    (net (code "45") (name "a") (class "Default")
      (node (ref "DB1") (pin "5") (pinfunction "A_5") (pintype "unspecified"))
      (node (ref "U1") (pin "10") (pinfunction "IO17_10") (pintype "unspecified"))
    )
    (net (code "46") (name "b") (class "Default")
      (node (ref "DB1") (pin "12") (pinfunction "B_12") (pintype "unspecified"))
      (node (ref "U1") (pin "9") (pinfunction "IO16_9") (pintype "unspecified"))
    )
    (net (code "47") (name "b1") (class "Default")
      (node (ref "DB1") (pin "2") (pinfunction "B1_2") (pintype "unspecified"))
      (node (ref "U1") (pin "18") (pinfunction "IO10_18") (pintype "unspecified"))
    )
    (net (code "48") (name "b2") (class "Default")
      (node (ref "DB1") (pin "4") (pinfunction "B2_4") (pintype "unspecified"))
      (node (ref "U1") (pin "11") (pinfunction "IO18_11") (pintype "unspecified"))
    )
    (net (code "49") (name "button") (class "Default")
      (node (ref "R14") (pin "1") (pinfunction "1_1") (pintype "input"))
      (node (ref "U1") (pin "32") (pinfunction "IO39_32") (pintype "unspecified"))
      (node (ref "U15") (pin "3") (pinfunction "3_3") (pintype "unspecified"))
      (node (ref "U15") (pin "4") (pinfunction "4_4") (pintype "unspecified"))
    )
    (net (code "50") (name "buzz") (class "Default")
      (node (ref "BUZZER") (pin "1") (pinfunction "1_1") (pintype "unspecified"))
      (node (ref "U1") (pin "33") (pinfunction "IO40_33") (pintype "unspecified"))
    )
    (net (code "51") (name "c") (class "Default")
      (node (ref "DB1") (pin "6") (pinfunction "C_6") (pintype "unspecified"))
      (node (ref "U1") (pin "8") (pinfunction "IO15_8") (pintype "unspecified"))
    )
    (net (code "52") (name "clk") (class "Default")
      (node (ref "DB1") (pin "7") (pinfunction "CLK_7") (pintype "unspecified"))
      (node (ref "U1") (pin "6") (pinfunction "IO6_6") (pintype "unspecified"))
    )
    (net (code "53") (name "d") (class "Default")
      (node (ref "DB1") (pin "11") (pinfunction "D_11") (pintype "unspecified"))
      (node (ref "U1") (pin "7") (pinfunction "IO7_7") (pintype "unspecified"))
    )
    (net (code "54") (name "g1") (class "Default")
      (node (ref "DB1") (pin "16") (pinfunction "G1_16") (pintype "unspecified"))
      (node (ref "U1") (pin "19") (pinfunction "IO11_19") (pintype "unspecified"))
    )
    (net (code "55") (name "g2") (class "Default")
      (node (ref "DB1") (pin "14") (pinfunction "G2_14") (pintype "unspecified"))
      (node (ref "U1") (pin "13") (pinfunction "IO19_13") (pintype "unspecified"))
    )
    (net (code "56") (name "lat") (class "Default")
      (node (ref "DB1") (pin "10") (pinfunction "LAT_10") (pintype "unspecified"))
      (node (ref "U1") (pin "5") (pinfunction "IO5_5") (pintype "unspecified"))
    )
    (net (code "57") (name "led_0_1") (class "Default")
      (node (ref "D10") (pin "1") (pinfunction "C_1") (pintype "unspecified"))
      (node (ref "LED1") (pin "2") (pinfunction "2_2") (pintype "unspecified"))
      (node (ref "U1") (pin "34") (pinfunction "IO41_34") (pintype "unspecified"))
    )
    (net (code "58") (name "led_0_2") (class "Default")
      (node (ref "D1") (pin "1") (pinfunction "C_1") (pintype "unspecified"))
      (node (ref "LED2") (pin "2") (pinfunction "2_2") (pintype "unspecified"))
      (node (ref "U1") (pin "35") (pinfunction "IO42_35") (pintype "unspecified"))
    )
    (net (code "59") (name "oe") (class "Default")
      (node (ref "DB1") (pin "8") (pinfunction "OE_8") (pintype "unspecified"))
      (node (ref "U1") (pin "4") (pinfunction "IO4_4") (pintype "unspecified"))
    )
    (net (code "60") (name "r1") (class "Default")
      (node (ref "DB1") (pin "1") (pinfunction "R1_1") (pintype "unspecified"))
      (node (ref "U1") (pin "20") (pinfunction "IO12_20") (pintype "unspecified"))
    )
    (net (code "61") (name "r2") (class "Default")
      (node (ref "DB1") (pin "3") (pinfunction "R2_3") (pintype "unspecified"))
      (node (ref "U1") (pin "14") (pinfunction "IO20_14") (pintype "unspecified"))
    )
    (net (code "62") (name "strapping46") (class "Default")
      (node (ref "R2") (pin "1") (pinfunction "1_1") (pintype "unspecified"))
      (node (ref "U1") (pin "16") (pinfunction "IO46_16") (pintype "unspecified"))
    )
    (net (code "63") (name "unconnected-(BUZZER-Pad3)") (class "Default")
      (node (ref "BUZZER") (pin "3") (pinfunction "3_3") (pintype "unspecified+no_connect"))
    )
    (net (code "64") (name "unconnected-(BUZZER-Pad4)") (class "Default")
      (node (ref "BUZZER") (pin "4") (pinfunction "4_4") (pintype "unspecified+no_connect"))
    )
    (net (code "65") (name "unconnected-(TF1-CD-Pad9)") (class "Default")
      (node (ref "TF1") (pin "9") (pinfunction "CD_9") (pintype "unspecified+no_connect"))
    )
    (net (code "66") (name "unconnected-(TF1-DAT1-Pad8)") (class "Default")
      (node (ref "TF1") (pin "8") (pinfunction "DAT1_8") (pintype "unspecified+no_connect"))
    )
    (net (code "67") (name "unconnected-(TF1-DAT2-Pad1)") (class "Default")
      (node (ref "TF1") (pin "1") (pinfunction "DAT2_1") (pintype "unspecified+no_connect"))
    )
    (net (code "68") (name "unconnected-(U1-IO35-Pad28)") (class "Default")
      (node (ref "U1") (pin "28") (pinfunction "IO35_28") (pintype "unspecified+no_connect"))
    )
    (net (code "69") (name "unconnected-(U1-IO36-Pad29)") (class "Default")
      (node (ref "U1") (pin "29") (pinfunction "IO36_29") (pintype "unspecified+no_connect"))
    )
    (net (code "70") (name "unconnected-(U1-IO37-Pad30)") (class "Default")
      (node (ref "U1") (pin "30") (pinfunction "IO37_30") (pintype "unspecified+no_connect"))
    )
    (net (code "71") (name "unconnected-(U1-IO45-Pad26)") (class "Default")
      (node (ref "U1") (pin "26") (pinfunction "IO45_26") (pintype "unspecified+no_connect"))
    )
    (net (code "72") (name "unconnected-(U2-PG-Pad10)") (class "Default")
      (node (ref "U2") (pin "10") (pinfunction "PG_10") (pintype "unspecified+no_connect"))
    )
    (net (code "73") (name "unconnected-(U6-CTS#-Pad9)") (class "Default")
      (node (ref "U6") (pin "9") (pinfunction "CTS#_9") (pintype "unspecified+no_connect"))
    )
    (net (code "74") (name "unconnected-(U6-DCD#-Pad12)") (class "Default")
      (node (ref "U6") (pin "12") (pinfunction "DCD#_12") (pintype "unspecified+no_connect"))
    )
    (net (code "75") (name "unconnected-(U6-DSR#-Pad10)") (class "Default")
      (node (ref "U6") (pin "10") (pinfunction "DSR#_10") (pintype "unspecified+no_connect"))
    )
    (net (code "76") (name "unconnected-(U6-NC.-Pad7)") (class "Default")
      (node (ref "U6") (pin "7") (pinfunction "NC._7") (pintype "unspecified+no_connect"))
    )
    (net (code "77") (name "unconnected-(U6-OUT#-Pad8)") (class "Default")
      (node (ref "U6") (pin "8") (pinfunction "OUT#_8") (pintype "unspecified+no_connect"))
    )
    (net (code "78") (name "unconnected-(U6-R232-Pad15)") (class "Default")
      (node (ref "U6") (pin "15") (pinfunction "R232_15") (pintype "unspecified+no_connect"))
    )
    (net (code "79") (name "unconnected-(U6-RI#-Pad11)") (class "Default")
      (node (ref "U6") (pin "11") (pinfunction "RI#_11") (pintype "unspecified+no_connect"))
    )
    (net (code "80") (name "unconnected-(USB3-ID-Pad4)") (class "Default")
      (node (ref "USB3") (pin "4") (pinfunction "ID_4") (pintype "unspecified+no_connect"))
    )
  )
)
